# NixieDriver_mx.net
KiCad netlist of a schematic drawn in EAGLE
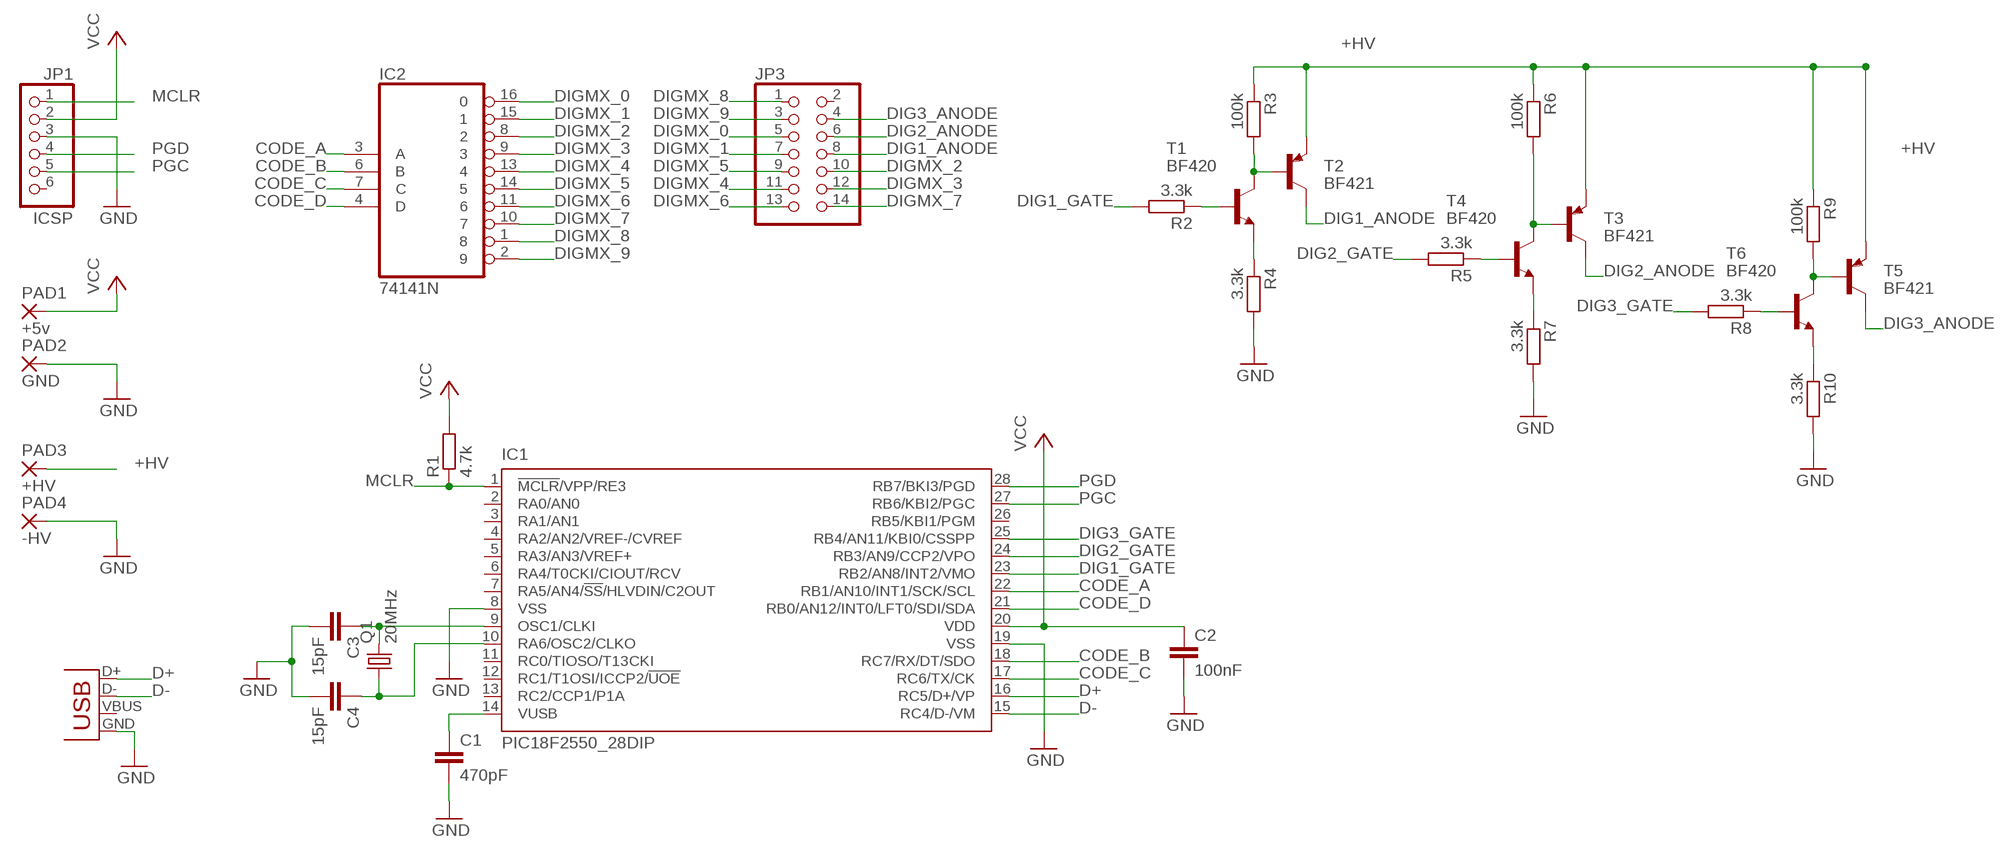
[diagram p0: schematic, sheet 1]

(export (version "E")
  (design (tool "Eeschema 10.0.6"))
  (components
    (comp (ref "C1")
      (value "470pF")
      (footprint "eagle-import:C050-024X044")
      (libsource (lib "eagle-import") (part "C-EU050-024X044"))
    )
    (comp (ref "C2")
      (value "100nF")
      (footprint "eagle-import:C050-024X044")
      (libsource (lib "eagle-import") (part "C-EU050-024X044"))
    )
    (comp (ref "C3")
      (value "15pF")
      (footprint "eagle-import:C050-024X044")
      (libsource (lib "eagle-import") (part "C-EU050-024X044"))
    )
    (comp (ref "C4")
      (value "15pF")
      (footprint "eagle-import:C050-024X044")
      (libsource (lib "eagle-import") (part "C-EU050-024X044"))
    )
    (comp (ref "IC1")
      (value "PIC18F2550_28DIP")
      (footprint "eagle-import:DIL28-3")
      (fields (field (name "MF") "MICROCHIP") (field (name "MPN") "PIC18F2550-I/SP"))
      (libsource (lib "eagle-import") (part "PIC18F2_28DIP550"))
    )
    (comp (ref "IC2")
      (value "74141N")
      (footprint "eagle-import:DIL16")
      (libsource (lib "eagle-import") (part "74141N"))
    )
    (comp (ref "JP1")
      (value "ICSP")
      (footprint "eagle-import:1X06")
      (libsource (lib "eagle-import") (part "PINHD-1X6"))
    )
    (comp (ref "JP3")
      (value "PINHD-2X7")
      (footprint "eagle-import:2X07")
      (libsource (lib "eagle-import") (part "PINHD-2X7"))
    )
    (comp (ref "PAD1")
      (value "+5v")
      (footprint "eagle-import:SMD2,54-5,08")
      (libsource (lib "eagle-import") (part "SMD5"))
    )
    (comp (ref "PAD2")
      (value "GND")
      (footprint "eagle-import:SMD2,54-5,08")
      (libsource (lib "eagle-import") (part "SMD5"))
    )
    (comp (ref "PAD3")
      (value "+HV")
      (footprint "eagle-import:SMD2,54-5,08")
      (libsource (lib "eagle-import") (part "SMD5"))
    )
    (comp (ref "PAD4")
      (value "-HV")
      (footprint "eagle-import:SMD2,54-5,08")
      (libsource (lib "eagle-import") (part "SMD5"))
    )
    (comp (ref "Q1")
      (value "20MHz")
      (footprint "eagle-import:HC49_S")
      (libsource (lib "eagle-import") (part "CRYSTALHC49S"))
    )
    (comp (ref "R1")
      (value "4.7k")
      (footprint "eagle-import:0207_2V")
      (libsource (lib "eagle-import") (part "R-EU_0207/2V"))
    )
    (comp (ref "R2")
      (value "3.3k")
      (footprint "eagle-import:0207_2V")
      (libsource (lib "eagle-import") (part "R-EU_0207/2V"))
    )
    (comp (ref "R3")
      (value "100k")
      (footprint "eagle-import:0207_5V")
      (libsource (lib "eagle-import") (part "R-EU_0207/5V"))
    )
    (comp (ref "R4")
      (value "3.3k")
      (footprint "eagle-import:0207_7")
      (libsource (lib "eagle-import") (part "R-EU_0207/7"))
    )
    (comp (ref "R5")
      (value "3.3k")
      (footprint "eagle-import:0207_2V")
      (libsource (lib "eagle-import") (part "R-EU_0207/2V"))
    )
    (comp (ref "R6")
      (value "100k")
      (footprint "eagle-import:0207_5V")
      (libsource (lib "eagle-import") (part "R-EU_0207/5V"))
    )
    (comp (ref "R7")
      (value "3.3k")
      (footprint "eagle-import:0207_7")
      (libsource (lib "eagle-import") (part "R-EU_0207/7"))
    )
    (comp (ref "R8")
      (value "3.3k")
      (footprint "eagle-import:0207_2V")
      (libsource (lib "eagle-import") (part "R-EU_0207/2V"))
    )
    (comp (ref "R9")
      (value "100k")
      (footprint "eagle-import:0207_5V")
      (libsource (lib "eagle-import") (part "R-EU_0207/5V"))
    )
    (comp (ref "R10")
      (value "3.3k")
      (footprint "eagle-import:0207_7")
      (libsource (lib "eagle-import") (part "R-EU_0207/7"))
    )
    (comp (ref "T1")
      (value "BF420")
      (footprint "eagle-import:TO92-ECB")
      (libsource (lib "eagle-import") (part "-NPN-TO92-ECBBC368"))
    )
    (comp (ref "T2")
      (value "BF421")
      (footprint "eagle-import:TO92-ECB")
      (libsource (lib "eagle-import") (part "-PNP-TO92-ECB"))
    )
    (comp (ref "T3")
      (value "BF421")
      (footprint "eagle-import:TO92-ECB")
      (libsource (lib "eagle-import") (part "-PNP-TO92-ECB"))
    )
    (comp (ref "T4")
      (value "BF420")
      (footprint "eagle-import:TO92-ECB")
      (libsource (lib "eagle-import") (part "-NPN-TO92-ECBBC368"))
    )
    (comp (ref "T5")
      (value "BF421")
      (footprint "eagle-import:TO92-ECB")
      (libsource (lib "eagle-import") (part "-PNP-TO92-ECB"))
    )
    (comp (ref "T6")
      (value "BF420")
      (footprint "eagle-import:TO92-ECB")
      (libsource (lib "eagle-import") (part "-NPN-TO92-ECBBC368"))
    )
    (comp (ref "X1")
      (value "USB-B-H")
      (footprint "eagle-import:USB-B-H")
      (libsource (lib "eagle-import") (part "USB-B-H"))
    )
  )
  (nets
    (net (code "1") (name "/+HV") (class "Default")
      (node (ref "PAD3") (pin "1") (pinfunction "P_1") (pintype "passive"))
      (node (ref "R3") (pin "1") (pinfunction "1_1") (pintype "passive"))
      (node (ref "R6") (pin "1") (pinfunction "1_1") (pintype "passive"))
      (node (ref "R9") (pin "1") (pinfunction "1_1") (pintype "passive"))
      (node (ref "T2") (pin "E") (pinfunction "E_E") (pintype "passive"))
      (node (ref "T3") (pin "E") (pinfunction "E_E") (pintype "passive"))
      (node (ref "T5") (pin "E") (pinfunction "E_E") (pintype "passive"))
    )
    (net (code "2") (name "/CODE_A") (class "Default")
      (node (ref "IC1") (pin "22") (pinfunction "RB1/AN10/INT1/SCK/SCL_22") (pintype "bidirectional"))
      (node (ref "IC2") (pin "3") (pinfunction "A_3") (pintype "input"))
    )
    (net (code "3") (name "/CODE_B") (class "Default")
      (node (ref "IC1") (pin "18") (pinfunction "RC7/RX/DT/SDO_18") (pintype "bidirectional"))
      (node (ref "IC2") (pin "6") (pinfunction "B_6") (pintype "input"))
    )
    (net (code "4") (name "/CODE_C") (class "Default")
      (node (ref "IC1") (pin "17") (pinfunction "RC6/TX/CK_17") (pintype "bidirectional"))
      (node (ref "IC2") (pin "7") (pinfunction "C_7") (pintype "input"))
    )
    (net (code "5") (name "/CODE_D") (class "Default")
      (node (ref "IC1") (pin "21") (pinfunction "RB0/AN12/INT0/LFT0/SDI/SDA_21") (pintype "bidirectional"))
      (node (ref "IC2") (pin "4") (pinfunction "D_4") (pintype "input"))
    )
    (net (code "6") (name "/D+") (class "Default")
      (node (ref "IC1") (pin "16") (pinfunction "RC5/D+/VP_16") (pintype "bidirectional"))
      (node (ref "X1") (pin "D+") (pinfunction "D+_D+") (pintype "bidirectional"))
    )
    (net (code "7") (name "/D-") (class "Default")
      (node (ref "IC1") (pin "15") (pinfunction "RC4/D-/VM_15") (pintype "bidirectional"))
      (node (ref "X1") (pin "D-") (pinfunction "D-_D-") (pintype "bidirectional"))
    )
    (net (code "8") (name "/DIG1_ANODE") (class "Default")
      (node (ref "JP3") (pin "8") (pinfunction "8_8") (pintype "passive"))
      (node (ref "T2") (pin "C") (pinfunction "C_C") (pintype "passive"))
    )
    (net (code "9") (name "/DIG1_GATE") (class "Default")
      (node (ref "IC1") (pin "23") (pinfunction "RB2/AN8/INT2/VMO_23") (pintype "bidirectional"))
      (node (ref "R2") (pin "2") (pinfunction "2_2") (pintype "passive"))
    )
    (net (code "10") (name "/DIG2_ANODE") (class "Default")
      (node (ref "JP3") (pin "6") (pinfunction "6_6") (pintype "passive"))
      (node (ref "T3") (pin "C") (pinfunction "C_C") (pintype "passive"))
    )
    (net (code "11") (name "/DIG2_GATE") (class "Default")
      (node (ref "IC1") (pin "24") (pinfunction "RB3/AN9/CCP2/VPO_24") (pintype "bidirectional"))
      (node (ref "R5") (pin "2") (pinfunction "2_2") (pintype "passive"))
    )
    (net (code "12") (name "/DIG3_ANODE") (class "Default")
      (node (ref "JP3") (pin "4") (pinfunction "4_4") (pintype "passive"))
      (node (ref "T5") (pin "C") (pinfunction "C_C") (pintype "passive"))
    )
    (net (code "13") (name "/DIG3_GATE") (class "Default")
      (node (ref "IC1") (pin "25") (pinfunction "RB4/AN11/KBI0/CSSPP_25") (pintype "bidirectional"))
      (node (ref "R8") (pin "2") (pinfunction "2_2") (pintype "passive"))
    )
    (net (code "14") (name "/DIGMX_0") (class "Default")
      (node (ref "IC2") (pin "16") (pinfunction "0_16") (pintype "open_collector"))
      (node (ref "JP3") (pin "5") (pinfunction "5_5") (pintype "passive"))
    )
    (net (code "15") (name "/DIGMX_1") (class "Default")
      (node (ref "IC2") (pin "15") (pinfunction "1_15") (pintype "open_collector"))
      (node (ref "JP3") (pin "7") (pinfunction "7_7") (pintype "passive"))
    )
    (net (code "16") (name "/DIGMX_2") (class "Default")
      (node (ref "IC2") (pin "8") (pinfunction "2_8") (pintype "open_collector"))
      (node (ref "JP3") (pin "10") (pinfunction "10_10") (pintype "passive"))
    )
    (net (code "17") (name "/DIGMX_3") (class "Default")
      (node (ref "IC2") (pin "9") (pinfunction "3_9") (pintype "open_collector"))
      (node (ref "JP3") (pin "12") (pinfunction "12_12") (pintype "passive"))
    )
    (net (code "18") (name "/DIGMX_4") (class "Default")
      (node (ref "IC2") (pin "13") (pinfunction "4_13") (pintype "open_collector"))
      (node (ref "JP3") (pin "11") (pinfunction "11_11") (pintype "passive"))
    )
    (net (code "19") (name "/DIGMX_5") (class "Default")
      (node (ref "IC2") (pin "14") (pinfunction "5_14") (pintype "open_collector"))
      (node (ref "JP3") (pin "9") (pinfunction "9_9") (pintype "passive"))
    )
    (net (code "20") (name "/DIGMX_6") (class "Default")
      (node (ref "IC2") (pin "11") (pinfunction "6_11") (pintype "open_collector"))
      (node (ref "JP3") (pin "13") (pinfunction "13_13") (pintype "passive"))
    )
    (net (code "21") (name "/DIGMX_7") (class "Default")
      (node (ref "IC2") (pin "10") (pinfunction "7_10") (pintype "open_collector"))
      (node (ref "JP3") (pin "14") (pinfunction "14_14") (pintype "passive"))
    )
    (net (code "22") (name "/DIGMX_8") (class "Default")
      (node (ref "IC2") (pin "1") (pinfunction "8_1") (pintype "open_collector"))
      (node (ref "JP3") (pin "1") (pinfunction "1_1") (pintype "passive"))
    )
    (net (code "23") (name "/DIGMX_9") (class "Default")
      (node (ref "IC2") (pin "2") (pinfunction "9_2") (pintype "open_collector"))
      (node (ref "JP3") (pin "3") (pinfunction "3_3") (pintype "passive"))
    )
    (net (code "24") (name "/MCLR") (class "Default")
      (node (ref "IC1") (pin "1") (pinfunction "~{MCLR}/VPP/RE3_1") (pintype "input"))
      (node (ref "JP1") (pin "1") (pinfunction "1_1") (pintype "passive"))
      (node (ref "R1") (pin "1") (pinfunction "1_1") (pintype "passive"))
    )
    (net (code "25") (name "/PGC") (class "Default")
      (node (ref "IC1") (pin "27") (pinfunction "RB6/KBI2/PGC_27") (pintype "bidirectional"))
      (node (ref "JP1") (pin "5") (pinfunction "5_5") (pintype "passive"))
    )
    (net (code "26") (name "/PGD") (class "Default")
      (node (ref "IC1") (pin "28") (pinfunction "RB7/BKI3/PGD_28") (pintype "bidirectional"))
      (node (ref "JP1") (pin "4") (pinfunction "4_4") (pintype "passive"))
    )
    (net (code "27") (name "GND") (class "Default")
      (node (ref "C1") (pin "2") (pinfunction "2_2") (pintype "passive"))
      (node (ref "C2") (pin "2") (pinfunction "2_2") (pintype "passive"))
      (node (ref "C3") (pin "2") (pinfunction "2_2") (pintype "passive"))
      (node (ref "C4") (pin "2") (pinfunction "2_2") (pintype "passive"))
      (node (ref "IC1") (pin "19") (pinfunction "VSS_19") (pintype "power_in"))
      (node (ref "IC1") (pin "8") (pinfunction "VSS_8") (pintype "power_in"))
      (node (ref "JP1") (pin "3") (pinfunction "3_3") (pintype "passive"))
      (node (ref "PAD2") (pin "1") (pinfunction "P_1") (pintype "passive"))
      (node (ref "PAD4") (pin "1") (pinfunction "P_1") (pintype "passive"))
      (node (ref "R10") (pin "2") (pinfunction "2_2") (pintype "passive"))
      (node (ref "R4") (pin "2") (pinfunction "2_2") (pintype "passive"))
      (node (ref "R7") (pin "2") (pinfunction "2_2") (pintype "passive"))
      (node (ref "X1") (pin "GND") (pinfunction "GND_GND") (pintype "bidirectional"))
    )
    (net (code "28") (name "Net-(IC1-OSC1{slash}CLKI)") (class "Default")
      (node (ref "C3") (pin "1") (pinfunction "1_1") (pintype "passive"))
      (node (ref "IC1") (pin "9") (pinfunction "OSC1/CLKI_9") (pintype "input"))
      (node (ref "Q1") (pin "2") (pinfunction "2_2") (pintype "passive"))
    )
    (net (code "29") (name "Net-(IC1-RA6{slash}OSC2{slash}CLKO)") (class "Default")
      (node (ref "C4") (pin "1") (pinfunction "1_1") (pintype "passive"))
      (node (ref "IC1") (pin "10") (pinfunction "RA6/OSC2/CLKO_10") (pintype "output"))
      (node (ref "Q1") (pin "1") (pinfunction "1_1") (pintype "passive"))
    )
    (net (code "30") (name "Net-(IC1-VUSB)") (class "Default")
      (node (ref "C1") (pin "1") (pinfunction "1_1") (pintype "passive"))
      (node (ref "IC1") (pin "14") (pinfunction "VUSB_14") (pintype "bidirectional"))
    )
    (net (code "31") (name "Net-(R2-Pad1)") (class "Default")
      (node (ref "R2") (pin "1") (pinfunction "1_1") (pintype "passive"))
      (node (ref "T1") (pin "B") (pinfunction "B_B") (pintype "passive"))
    )
    (net (code "32") (name "Net-(R3-Pad2)") (class "Default")
      (node (ref "R3") (pin "2") (pinfunction "2_2") (pintype "passive"))
      (node (ref "T1") (pin "C") (pinfunction "C_C") (pintype "passive"))
      (node (ref "T2") (pin "B") (pinfunction "B_B") (pintype "passive"))
    )
    (net (code "33") (name "Net-(R4-Pad1)") (class "Default")
      (node (ref "R4") (pin "1") (pinfunction "1_1") (pintype "passive"))
      (node (ref "T1") (pin "E") (pinfunction "E_E") (pintype "passive"))
    )
    (net (code "34") (name "Net-(R5-Pad1)") (class "Default")
      (node (ref "R5") (pin "1") (pinfunction "1_1") (pintype "passive"))
      (node (ref "T4") (pin "B") (pinfunction "B_B") (pintype "passive"))
    )
    (net (code "35") (name "Net-(R6-Pad2)") (class "Default")
      (node (ref "R6") (pin "2") (pinfunction "2_2") (pintype "passive"))
      (node (ref "T3") (pin "B") (pinfunction "B_B") (pintype "passive"))
      (node (ref "T4") (pin "C") (pinfunction "C_C") (pintype "passive"))
    )
    (net (code "36") (name "Net-(R7-Pad1)") (class "Default")
      (node (ref "R7") (pin "1") (pinfunction "1_1") (pintype "passive"))
      (node (ref "T4") (pin "E") (pinfunction "E_E") (pintype "passive"))
    )
    (net (code "37") (name "Net-(R8-Pad1)") (class "Default")
      (node (ref "R8") (pin "1") (pinfunction "1_1") (pintype "passive"))
      (node (ref "T6") (pin "B") (pinfunction "B_B") (pintype "passive"))
    )
    (net (code "38") (name "Net-(R9-Pad2)") (class "Default")
      (node (ref "R9") (pin "2") (pinfunction "2_2") (pintype "passive"))
      (node (ref "T5") (pin "B") (pinfunction "B_B") (pintype "passive"))
      (node (ref "T6") (pin "C") (pinfunction "C_C") (pintype "passive"))
    )
    (net (code "39") (name "Net-(R10-Pad1)") (class "Default")
      (node (ref "R10") (pin "1") (pinfunction "1_1") (pintype "passive"))
      (node (ref "T6") (pin "E") (pinfunction "E_E") (pintype "passive"))
    )
    (net (code "40") (name "VCC") (class "Default")
      (node (ref "C2") (pin "1") (pinfunction "1_1") (pintype "passive"))
      (node (ref "IC1") (pin "20") (pinfunction "VDD_20") (pintype "power_in"))
      (node (ref "JP1") (pin "2") (pinfunction "2_2") (pintype "passive"))
      (node (ref "PAD1") (pin "1") (pinfunction "P_1") (pintype "passive"))
      (node (ref "R1") (pin "2") (pinfunction "2_2") (pintype "passive"))
    )
    (net (code "41") (name "unconnected-(IC1-RA0{slash}AN0-Pad2)") (class "Default")
      (node (ref "IC1") (pin "2") (pinfunction "RA0/AN0_2") (pintype "bidirectional"))
    )
    (net (code "42") (name "unconnected-(IC1-RA1{slash}AN1-Pad3)") (class "Default")
      (node (ref "IC1") (pin "3") (pinfunction "RA1/AN1_3") (pintype "bidirectional"))
    )
    (net (code "43") (name "unconnected-(IC1-RA2{slash}AN2{slash}VREF-{slash}CVREF-Pad4)") (class "Default")
      (node (ref "IC1") (pin "4") (pinfunction "RA2/AN2/VREF-/CVREF_4") (pintype "bidirectional"))
    )
    (net (code "44") (name "unconnected-(IC1-RA3{slash}AN3{slash}VREF+-Pad5)") (class "Default")
      (node (ref "IC1") (pin "5") (pinfunction "RA3/AN3/VREF+_5") (pintype "bidirectional"))
    )
    (net (code "45") (name "unconnected-(IC1-RA4{slash}T0CKI{slash}CIOUT{slash}RCV-Pad6)") (class "Default")
      (node (ref "IC1") (pin "6") (pinfunction "RA4/T0CKI/CIOUT/RCV_6") (pintype "bidirectional"))
    )
    (net (code "46") (name "unconnected-(IC1-RA5{slash}AN4{slash}~{SS}{slash}HLVDIN{slash}C2OUT-Pad7)") (class "Default")
      (node (ref "IC1") (pin "7") (pinfunction "RA5/AN4/~{SS}/HLVDIN/C2OUT_7") (pintype "bidirectional"))
    )
    (net (code "47") (name "unconnected-(IC1-RB5{slash}KBI1{slash}PGM-Pad26)") (class "Default")
      (node (ref "IC1") (pin "26") (pinfunction "RB5/KBI1/PGM_26") (pintype "bidirectional"))
    )
    (net (code "48") (name "unconnected-(IC1-RC0{slash}TIOSO{slash}T13CKI-Pad11)") (class "Default")
      (node (ref "IC1") (pin "11") (pinfunction "RC0/TIOSO/T13CKI_11") (pintype "bidirectional"))
    )
    (net (code "49") (name "unconnected-(IC1-RC1{slash}T1OSI{slash}ICCP2{slash}~{UOE}-Pad12)") (class "Default")
      (node (ref "IC1") (pin "12") (pinfunction "RC1/T1OSI/ICCP2/~{UOE}_12") (pintype "bidirectional"))
    )
    (net (code "50") (name "unconnected-(IC1-RC2{slash}CCP1{slash}P1A-Pad13)") (class "Default")
      (node (ref "IC1") (pin "13") (pinfunction "RC2/CCP1/P1A_13") (pintype "bidirectional"))
    )
    (net (code "51") (name "unconnected-(JP1-Pad6)") (class "Default")
      (node (ref "JP1") (pin "6") (pinfunction "6_6") (pintype "passive"))
    )
    (net (code "52") (name "unconnected-(JP3-Pad2)") (class "Default")
      (node (ref "JP3") (pin "2") (pinfunction "2_2") (pintype "passive"))
    )
    (net (code "53") (name "unconnected-(X1-PadVBUS)") (class "Default")
      (node (ref "X1") (pin "VBUS") (pinfunction "VBUS_VBUS") (pintype "bidirectional"))
    )
  )
)
